# Top_Level.net
KiCad netlist of a schematic drawn in Altium Designer
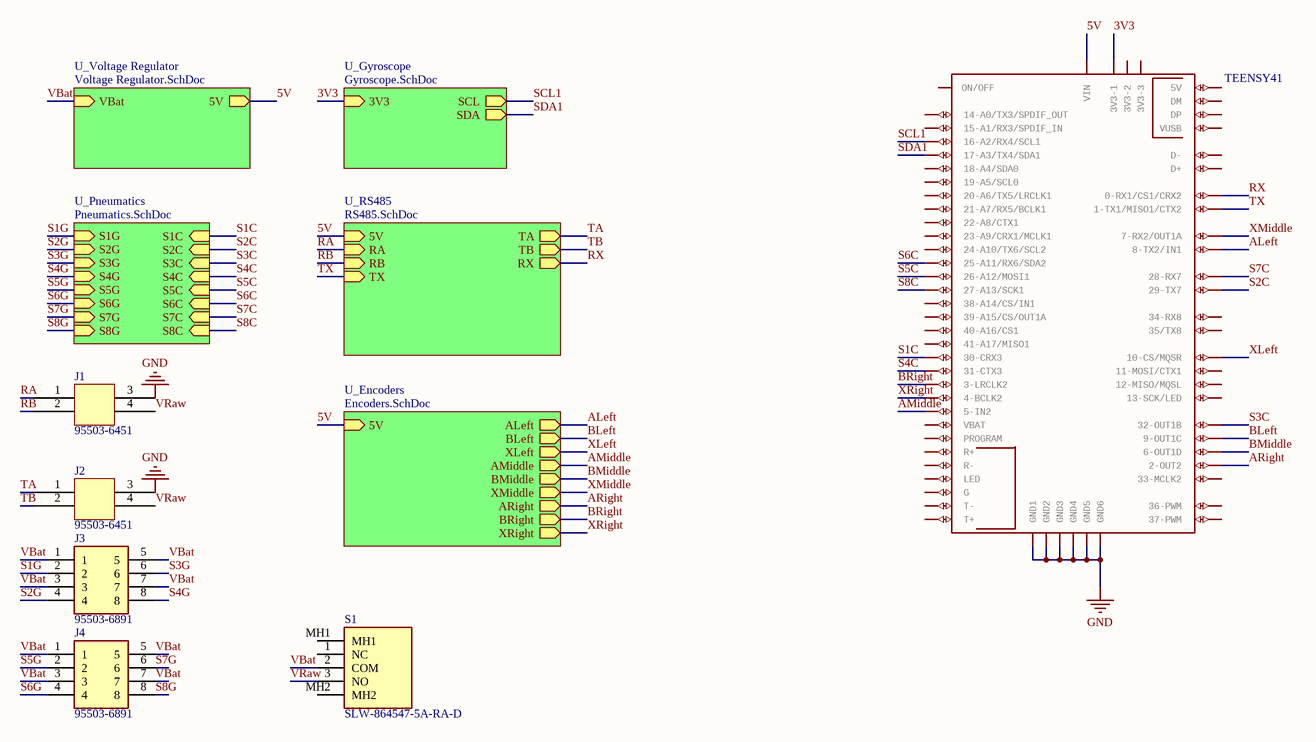
[diagram p0: Top Level.SchDoc]

(export (version "E")
  (design (tool "Eeschema 10.0.6"))
  (components
    (comp (ref "J1")
      (value "95503-6451")
      (footprint "95503-6451-Footprint-1")
      (libsource (lib "Jouveer") (part "95503-6451"))
    )
    (comp (ref "J2")
      (value "95503-6451")
      (footprint "95503-6451-Footprint-1")
      (libsource (lib "Jouveer") (part "95503-6451"))
    )
    (comp (ref "J3")
      (value "95503-6891")
      (footprint "95503-6891")
      (description "Connector")
      (fields (field (name "MOUSER PART NUMBER") "538-95503-6891"))
      (libsource (lib "*") (part "95503-6891"))
    )
    (comp (ref "J4")
      (value "95503-6891")
      (footprint "95503-6891")
      (description "Connector")
      (fields (field (name "MOUSER PART NUMBER") "538-95503-6891"))
      (libsource (lib "*") (part "95503-6891"))
    )
    (comp (ref "S1")
      (value "SLW-864547-5A-RA-D")
      (footprint "SLW8645475ARAD")
      (description "Switch")
      (fields (field (name "MOUSER PART NUMBER") "179-SLW-864547-5ARAD"))
      (libsource (lib "SamacSys") (part "SLW-864547-5A-RA-D"))
    )
    (comp (ref "U1")
      (value "TEENSY41")
      (footprint "TEENSY41")
      (description "Teensy 4.1 Development Board")
      (libsource (lib "Jason Zhou") (part "CMP-013-000002-2"))
    )
  )
  (nets
    (net (code "1") (name "/3V3") (class "Default")
      (node (ref "U1") (pin "3V3-1") (pinfunction "3V3-1_3V3-1") (pintype "bidirectional"))
    )
    (net (code "2") (name "/5V") (class "Default")
      (node (ref "U1") (pin "VIN") (pinfunction "VIN_VIN") (pintype "bidirectional"))
    )
    (net (code "3") (name "/ALeft") (class "Default")
      (node (ref "U1") (pin "8-TX2/IN1") (pinfunction "8-TX2/IN1_8-TX2/IN1") (pintype "bidirectional"))
    )
    (net (code "4") (name "/AMiddle") (class "Default")
      (node (ref "U1") (pin "5-IN2") (pinfunction "5-IN2_5-IN2") (pintype "bidirectional"))
    )
    (net (code "5") (name "/ARight") (class "Default")
      (node (ref "U1") (pin "2-OUT2") (pinfunction "2-OUT2_2-OUT2") (pintype "bidirectional"))
    )
    (net (code "6") (name "/BLeft") (class "Default")
      (node (ref "U1") (pin "9-OUT1C") (pinfunction "9-OUT1C_9-OUT1C") (pintype "bidirectional"))
    )
    (net (code "7") (name "/BMiddle") (class "Default")
      (node (ref "U1") (pin "6-OUT1D") (pinfunction "6-OUT1D_6-OUT1D") (pintype "bidirectional"))
    )
    (net (code "8") (name "/BRight") (class "Default")
      (node (ref "U1") (pin "3-LRCLK2") (pinfunction "3-LRCLK2_3-LRCLK2") (pintype "bidirectional"))
    )
    (net (code "9") (name "/RA") (class "Default")
      (node (ref "J1") (pin "1") (pinfunction "1_1") (pintype "passive"))
    )
    (net (code "10") (name "/RB") (class "Default")
      (node (ref "J1") (pin "2") (pinfunction "2_2") (pintype "passive"))
    )
    (net (code "11") (name "/RX") (class "Default")
      (node (ref "U1") (pin "0-RX1/CS1/CRX2") (pinfunction "0-RX1/CS1/CRX2_0-RX1/CS1/CRX2") (pintype "bidirectional"))
    )
    (net (code "12") (name "/S1C") (class "Default")
      (node (ref "U1") (pin "30-CRX3") (pinfunction "30-CRX3_30-CRX3") (pintype "bidirectional"))
    )
    (net (code "13") (name "/S1G") (class "Default")
      (node (ref "J3") (pin "2") (pinfunction "2_2") (pintype "passive"))
    )
    (net (code "14") (name "/S2C") (class "Default")
      (node (ref "U1") (pin "29-TX7") (pinfunction "29-TX7_29-TX7") (pintype "bidirectional"))
    )
    (net (code "15") (name "/S2G") (class "Default")
      (node (ref "J3") (pin "4") (pinfunction "4_4") (pintype "passive"))
    )
    (net (code "16") (name "/S3C") (class "Default")
      (node (ref "U1") (pin "32-OUT1B") (pinfunction "32-OUT1B_32-OUT1B") (pintype "bidirectional"))
    )
    (net (code "17") (name "/S3G") (class "Default")
      (node (ref "J3") (pin "6") (pinfunction "6_6") (pintype "passive"))
    )
    (net (code "18") (name "/S4C") (class "Default")
      (node (ref "U1") (pin "31-CTX3") (pinfunction "31-CTX3_31-CTX3") (pintype "bidirectional"))
    )
    (net (code "19") (name "/S4G") (class "Default")
      (node (ref "J3") (pin "8") (pinfunction "8_8") (pintype "passive"))
    )
    (net (code "20") (name "/S5C") (class "Default")
      (node (ref "U1") (pin "26-A12/MOSI1") (pinfunction "26-A12/MOSI1_26-A12/MOSI1") (pintype "bidirectional"))
    )
    (net (code "21") (name "/S5G") (class "Default")
      (node (ref "J4") (pin "2") (pinfunction "2_2") (pintype "passive"))
    )
    (net (code "22") (name "/S6C") (class "Default")
      (node (ref "U1") (pin "25-A11/RX6/SDA2") (pinfunction "25-A11/RX6/SDA2_25-A11/RX6/SDA2") (pintype "bidirectional"))
    )
    (net (code "23") (name "/S6G") (class "Default")
      (node (ref "J4") (pin "4") (pinfunction "4_4") (pintype "passive"))
    )
    (net (code "24") (name "/S7C") (class "Default")
      (node (ref "U1") (pin "28-RX7") (pinfunction "28-RX7_28-RX7") (pintype "bidirectional"))
    )
    (net (code "25") (name "/S7G") (class "Default")
      (node (ref "J4") (pin "6") (pinfunction "6_6") (pintype "passive"))
    )
    (net (code "26") (name "/S8C") (class "Default")
      (node (ref "U1") (pin "27-A13/SCK1") (pinfunction "27-A13/SCK1_27-A13/SCK1") (pintype "bidirectional"))
    )
    (net (code "27") (name "/S8G") (class "Default")
      (node (ref "J4") (pin "8") (pinfunction "8_8") (pintype "passive"))
    )
    (net (code "28") (name "/SCL1") (class "Default")
      (node (ref "U1") (pin "16-A2/RX4/SCL1") (pinfunction "16-A2/RX4/SCL1_16-A2/RX4/SCL1") (pintype "bidirectional"))
    )
    (net (code "29") (name "/SDA1") (class "Default")
      (node (ref "U1") (pin "17-A3/TX4/SDA1") (pinfunction "17-A3/TX4/SDA1_17-A3/TX4/SDA1") (pintype "bidirectional"))
    )
    (net (code "30") (name "/TA") (class "Default")
      (node (ref "J2") (pin "1") (pinfunction "1_1") (pintype "passive"))
    )
    (net (code "31") (name "/TB") (class "Default")
      (node (ref "J2") (pin "2") (pinfunction "2_2") (pintype "passive"))
    )
    (net (code "32") (name "/TX") (class "Default")
      (node (ref "U1") (pin "1-TX1/MISO1/CTX2") (pinfunction "1-TX1/MISO1/CTX2_1-TX1/MISO1/CTX2") (pintype "bidirectional"))
    )
    (net (code "33") (name "/VBat") (class "Default")
      (node (ref "J3") (pin "1") (pinfunction "1_1") (pintype "passive"))
      (node (ref "J3") (pin "3") (pinfunction "3_3") (pintype "passive"))
      (node (ref "J3") (pin "5") (pinfunction "5_5") (pintype "passive"))
      (node (ref "J3") (pin "7") (pinfunction "7_7") (pintype "passive"))
      (node (ref "J4") (pin "1") (pinfunction "1_1") (pintype "passive"))
      (node (ref "J4") (pin "3") (pinfunction "3_3") (pintype "passive"))
      (node (ref "J4") (pin "5") (pinfunction "5_5") (pintype "passive"))
      (node (ref "J4") (pin "7") (pinfunction "7_7") (pintype "passive"))
      (node (ref "S1") (pin "2") (pinfunction "COM_2") (pintype "passive"))
    )
    (net (code "34") (name "/VRaw") (class "Default")
      (node (ref "J1") (pin "4") (pinfunction "4_4") (pintype "passive"))
      (node (ref "J2") (pin "4") (pinfunction "4_4") (pintype "passive"))
      (node (ref "S1") (pin "3") (pinfunction "NO_3") (pintype "passive"))
    )
    (net (code "35") (name "/XLeft") (class "Default")
      (node (ref "U1") (pin "10-C~{S}MQSR") (pinfunction "10-CS/MQSR_10-C~{S}MQSR") (pintype "bidirectional"))
    )
    (net (code "36") (name "/XMiddle") (class "Default")
      (node (ref "U1") (pin "7-RX2/OUT1A") (pinfunction "7-RX2/OUT1A_7-RX2/OUT1A") (pintype "bidirectional"))
    )
    (net (code "37") (name "/XRight") (class "Default")
      (node (ref "U1") (pin "4-BCLK2") (pinfunction "4-BCLK2_4-BCLK2") (pintype "bidirectional"))
    )
    (net (code "38") (name "GND") (class "Default")
      (node (ref "J1") (pin "3") (pinfunction "3_3") (pintype "passive"))
      (node (ref "J2") (pin "3") (pinfunction "3_3") (pintype "passive"))
      (node (ref "U1") (pin "GND1") (pinfunction "GND1_GND1") (pintype "bidirectional"))
      (node (ref "U1") (pin "GND2") (pinfunction "GND2_GND2") (pintype "bidirectional"))
      (node (ref "U1") (pin "GND3") (pinfunction "GND3_GND3") (pintype "bidirectional"))
      (node (ref "U1") (pin "GND4") (pinfunction "GND4_GND4") (pintype "bidirectional"))
      (node (ref "U1") (pin "GND5") (pinfunction "GND5_GND5") (pintype "bidirectional"))
      (node (ref "U1") (pin "GND6") (pinfunction "GND6_GND6") (pintype "bidirectional"))
    )
    (net (code "39") (name "unconnected-(S1-NC-Pad1)") (class "Default")
      (node (ref "S1") (pin "1") (pinfunction "NC_1") (pintype "passive"))
    )
    (net (code "40") (name "unconnected-(S1-PadMH1)") (class "Default")
      (node (ref "S1") (pin "MH1") (pinfunction "MH1_MH1") (pintype "passive"))
    )
    (net (code "41") (name "unconnected-(S1-PadMH2)") (class "Default")
      (node (ref "S1") (pin "MH2") (pinfunction "MH2_MH2") (pintype "passive"))
    )
    (net (code "42") (name "unconnected-(U1-5V-Pad+5V)") (class "Default")
      (node (ref "U1") (pin "+5V") (pinfunction "5V_+5V") (pintype "bidirectional"))
    )
    (net (code "43") (name "unconnected-(U1-35{slash}TX8-Pad35-TX8)") (class "Default")
      (node (ref "U1") (pin "35-TX8") (pinfunction "35/TX8_35-TX8") (pintype "bidirectional"))
    )
    (net (code "44") (name "unconnected-(U1-Pad3V3-2)") (class "Default")
      (node (ref "U1") (pin "3V3-2") (pinfunction "3V3-2_3V3-2") (pintype "bidirectional"))
    )
    (net (code "45") (name "unconnected-(U1-Pad3V3-3)") (class "Default")
      (node (ref "U1") (pin "3V3-3") (pinfunction "3V3-3_3V3-3") (pintype "bidirectional"))
    )
    (net (code "46") (name "unconnected-(U1-Pad11-MOSI{slash}CTX1)") (class "Default")
      (node (ref "U1") (pin "11-MOSI/CTX1") (pinfunction "11-MOSI/CTX1_11-MOSI/CTX1") (pintype "bidirectional"))
    )
    (net (code "47") (name "unconnected-(U1-Pad12-MISO{slash}MQSL)") (class "Default")
      (node (ref "U1") (pin "12-MISO/MQSL") (pinfunction "12-MISO/MQSL_12-MISO/MQSL") (pintype "bidirectional"))
    )
    (net (code "48") (name "unconnected-(U1-Pad13-SCK{slash}LED)") (class "Default")
      (node (ref "U1") (pin "13-SCK/LED") (pinfunction "13-SCK/LED_13-SCK/LED") (pintype "bidirectional"))
    )
    (net (code "49") (name "unconnected-(U1-Pad14-A0{slash}TX3{slash}SPDIF_OUT)") (class "Default")
      (node (ref "U1") (pin "14-A0/TX3/SPDIF_OUT") (pinfunction "14-A0/TX3/SPDIF_OUT_14-A0/TX3/SPDIF_OUT") (pintype "bidirectional"))
    )
    (net (code "50") (name "unconnected-(U1-Pad15-A1{slash}RX3{slash}SPDIF_IN)") (class "Default")
      (node (ref "U1") (pin "15-A1/RX3/SPDIF_IN") (pinfunction "15-A1/RX3/SPDIF_IN_15-A1/RX3/SPDIF_IN") (pintype "bidirectional"))
    )
    (net (code "51") (name "unconnected-(U1-Pad18-A4{slash}SDA0)") (class "Default")
      (node (ref "U1") (pin "18-A4/SDA0") (pinfunction "18-A4/SDA0_18-A4/SDA0") (pintype "bidirectional"))
    )
    (net (code "52") (name "unconnected-(U1-Pad19-A5{slash}SCL0)") (class "Default")
      (node (ref "U1") (pin "19-A5/SCL0") (pinfunction "19-A5/SCL0_19-A5/SCL0") (pintype "bidirectional"))
    )
    (net (code "53") (name "unconnected-(U1-Pad20-A6{slash}TX5{slash}LRCLK1)") (class "Default")
      (node (ref "U1") (pin "20-A6/TX5/LRCLK1") (pinfunction "20-A6/TX5/LRCLK1_20-A6/TX5/LRCLK1") (pintype "bidirectional"))
    )
    (net (code "54") (name "unconnected-(U1-Pad21-A7{slash}RX5{slash}BCLK1)") (class "Default")
      (node (ref "U1") (pin "21-A7/RX5/BCLK1") (pinfunction "21-A7/RX5/BCLK1_21-A7/RX5/BCLK1") (pintype "bidirectional"))
    )
    (net (code "55") (name "unconnected-(U1-Pad22-A8{slash}CTX1)") (class "Default")
      (node (ref "U1") (pin "22-A8/CTX1") (pinfunction "22-A8/CTX1_22-A8/CTX1") (pintype "bidirectional"))
    )
    (net (code "56") (name "unconnected-(U1-Pad23-A9{slash}CRX1{slash}MCLK1)") (class "Default")
      (node (ref "U1") (pin "23-A9/CRX1/MCLK1") (pinfunction "23-A9/CRX1/MCLK1_23-A9/CRX1/MCLK1") (pintype "bidirectional"))
    )
    (net (code "57") (name "unconnected-(U1-Pad24-A10{slash}TX6{slash}SCL2)") (class "Default")
      (node (ref "U1") (pin "24-A10/TX6/SCL2") (pinfunction "24-A10/TX6/SCL2_24-A10/TX6/SCL2") (pintype "bidirectional"))
    )
    (net (code "58") (name "unconnected-(U1-Pad33-MCLK2)") (class "Default")
      (node (ref "U1") (pin "33-MCLK2") (pinfunction "33-MCLK2_33-MCLK2") (pintype "bidirectional"))
    )
    (net (code "59") (name "unconnected-(U1-Pad34-RX8)") (class "Default")
      (node (ref "U1") (pin "34-RX8") (pinfunction "34-RX8_34-RX8") (pintype "bidirectional"))
    )
    (net (code "60") (name "unconnected-(U1-Pad36-PWM)") (class "Default")
      (node (ref "U1") (pin "36-PWM") (pinfunction "36-PWM_36-PWM") (pintype "bidirectional"))
    )
    (net (code "61") (name "unconnected-(U1-Pad37-PWM)") (class "Default")
      (node (ref "U1") (pin "37-PWM") (pinfunction "37-PWM_37-PWM") (pintype "bidirectional"))
    )
    (net (code "62") (name "unconnected-(U1-Pad38-A14{slash}CS{slash}IN1)") (class "Default")
      (node (ref "U1") (pin "38-A14/CS/IN1") (pinfunction "38-A14/CS/IN1_38-A14/CS/IN1") (pintype "bidirectional"))
    )
    (net (code "63") (name "unconnected-(U1-Pad39-A15{slash}CS{slash}OUT1A)") (class "Default")
      (node (ref "U1") (pin "39-A15/CS/OUT1A") (pinfunction "39-A15/CS/OUT1A_39-A15/CS/OUT1A") (pintype "bidirectional"))
    )
    (net (code "64") (name "unconnected-(U1-Pad40-A16{slash}CS1)") (class "Default")
      (node (ref "U1") (pin "40-A16/CS1") (pinfunction "40-A16/CS1_40-A16/CS1") (pintype "bidirectional"))
    )
    (net (code "65") (name "unconnected-(U1-Pad41-A17{slash}MISO1)") (class "Default")
      (node (ref "U1") (pin "41-A17/MISO1") (pinfunction "41-A17/MISO1_41-A17/MISO1") (pintype "bidirectional"))
    )
    (net (code "66") (name "unconnected-(U1-PadD+)") (class "Default")
      (node (ref "U1") (pin "D+") (pinfunction "D+_D+") (pintype "bidirectional"))
    )
    (net (code "67") (name "unconnected-(U1-PadD-)") (class "Default")
      (node (ref "U1") (pin "D-") (pinfunction "D-_D-") (pintype "bidirectional"))
    )
    (net (code "68") (name "unconnected-(U1-PadDM)") (class "Default")
      (node (ref "U1") (pin "DM") (pinfunction "DM_DM") (pintype "bidirectional"))
    )
    (net (code "69") (name "unconnected-(U1-PadDP)") (class "Default")
      (node (ref "U1") (pin "DP") (pinfunction "DP_DP") (pintype "bidirectional"))
    )
    (net (code "70") (name "unconnected-(U1-PadG)") (class "Default")
      (node (ref "U1") (pin "G") (pinfunction "G_G") (pintype "bidirectional"))
    )
    (net (code "71") (name "unconnected-(U1-PadLED)") (class "Default")
      (node (ref "U1") (pin "LED") (pinfunction "LED_LED") (pintype "bidirectional"))
    )
    (net (code "72") (name "unconnected-(U1-PadON{slash}OFF)") (class "Default")
      (node (ref "U1") (pin "ON/OFF") (pinfunction "ON/OFF_ON/OFF") (pintype "bidirectional"))
    )
    (net (code "73") (name "unconnected-(U1-PadPROGRAM)") (class "Default")
      (node (ref "U1") (pin "PROGRAM") (pinfunction "PROGRAM_PROGRAM") (pintype "bidirectional"))
    )
    (net (code "74") (name "unconnected-(U1-PadR+)") (class "Default")
      (node (ref "U1") (pin "R+") (pinfunction "R+_R+") (pintype "bidirectional"))
    )
    (net (code "75") (name "unconnected-(U1-PadR-)") (class "Default")
      (node (ref "U1") (pin "R-") (pinfunction "R-_R-") (pintype "bidirectional"))
    )
    (net (code "76") (name "unconnected-(U1-PadT+)") (class "Default")
      (node (ref "U1") (pin "T+") (pinfunction "T+_T+") (pintype "bidirectional"))
    )
    (net (code "77") (name "unconnected-(U1-PadT-)") (class "Default")
      (node (ref "U1") (pin "T-") (pinfunction "T-_T-") (pintype "bidirectional"))
    )
    (net (code "78") (name "unconnected-(U1-PadVBAT)") (class "Default")
      (node (ref "U1") (pin "VBAT") (pinfunction "VBAT_VBAT") (pintype "bidirectional"))
    )
    (net (code "79") (name "unconnected-(U1-PadVUSB)") (class "Default")
      (node (ref "U1") (pin "VUSB") (pinfunction "VUSB_VUSB") (pintype "bidirectional"))
    )
  )
)
